# board1.net
KiCad netlist of a schematic drawn in EAGLE
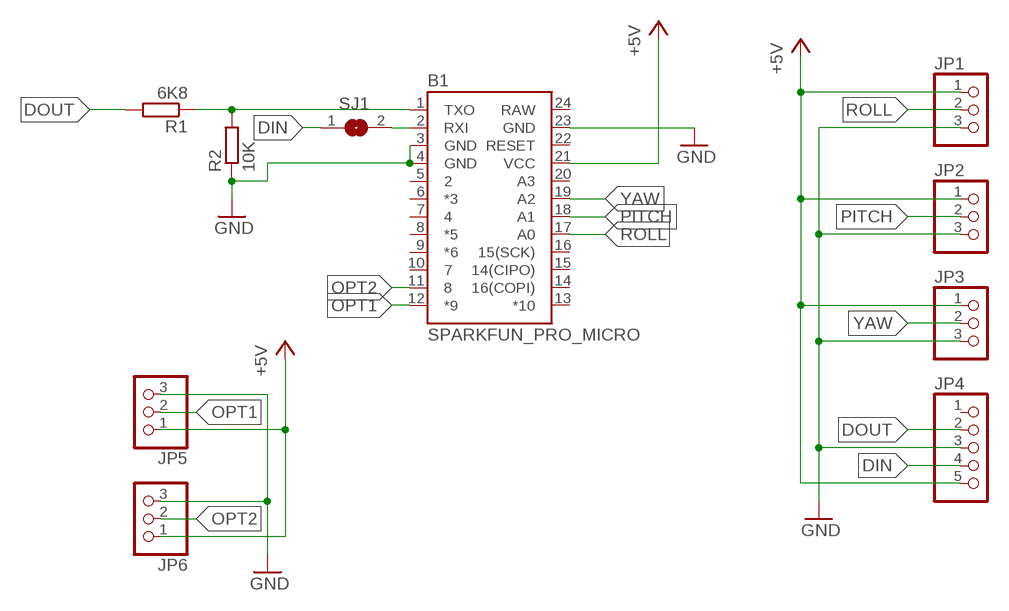
[diagram p0: schematic, sheet 1]

(export (version "E")
  (design (tool "Eeschema 10.0.6"))
  (components
    (comp (ref "B1")
      (value "SPARKFUN_PRO_MICRO")
      (footprint "eagle-import:SPARKFUN_PRO_MICRO")
      (libsource (lib "eagle-import") (part "SPARKFUN_PRO_MICRO"))
    )
    (comp (ref "JP1")
      (value "PINHD-1X3")
      (footprint "eagle-import:1X03")
      (libsource (lib "eagle-import") (part "PINHD-1X3"))
    )
    (comp (ref "JP2")
      (value "PINHD-1X3")
      (footprint "eagle-import:1X03")
      (libsource (lib "eagle-import") (part "PINHD-1X3"))
    )
    (comp (ref "JP3")
      (value "PINHD-1X3")
      (footprint "eagle-import:1X03")
      (libsource (lib "eagle-import") (part "PINHD-1X3"))
    )
    (comp (ref "JP4")
      (value "PINHD-1X5")
      (footprint "eagle-import:1X05")
      (libsource (lib "eagle-import") (part "PINHD-1X5"))
    )
    (comp (ref "JP5")
      (value "PINHD-1X3")
      (footprint "eagle-import:1X03")
      (libsource (lib "eagle-import") (part "PINHD-1X3"))
    )
    (comp (ref "JP6")
      (value "PINHD-1X3")
      (footprint "eagle-import:1X03")
      (libsource (lib "eagle-import") (part "PINHD-1X3"))
    )
    (comp (ref "R1")
      (value "6K8")
      (footprint "eagle-import:R0603")
      (libsource (lib "eagle-import") (part "R-EU_R0603"))
    )
    (comp (ref "R2")
      (value "10K")
      (footprint "eagle-import:R0603")
      (libsource (lib "eagle-import") (part "R-EU_R0603"))
    )
    (comp (ref "SJ1") (value "SJ") (footprint "eagle-import:SJ") (libsource (lib "eagle-import") (part "SJ")))
  )
  (nets
    (net (code "1") (name "+5V") (class "Default")
      (node (ref "B1") (pin "21") (pinfunction "VCC_21") (pintype "power_in"))
      (node (ref "JP1") (pin "1") (pinfunction "1_1") (pintype "passive"))
      (node (ref "JP2") (pin "1") (pinfunction "1_1") (pintype "passive"))
      (node (ref "JP3") (pin "1") (pinfunction "1_1") (pintype "passive"))
      (node (ref "JP4") (pin "5") (pinfunction "5_5") (pintype "passive"))
      (node (ref "JP5") (pin "1") (pinfunction "1_1") (pintype "passive"))
      (node (ref "JP6") (pin "1") (pinfunction "1_1") (pintype "passive"))
    )
    (net (code "2") (name "/RAW") (class "Default")
      (node (ref "B1") (pin "24") (pinfunction "RAW_24") (pintype "power_in"))
    )
    (net (code "3") (name "DIN") (class "Default")
      (node (ref "JP4") (pin "4") (pinfunction "4_4") (pintype "passive"))
      (node (ref "SJ1") (pin "1") (pinfunction "1_1") (pintype "passive"))
    )
    (net (code "4") (name "DOUT") (class "Default")
      (node (ref "JP4") (pin "2") (pinfunction "2_2") (pintype "passive"))
      (node (ref "R1") (pin "2") (pinfunction "2_2") (pintype "passive"))
    )
    (net (code "5") (name "GND") (class "Default")
      (node (ref "B1") (pin "23") (pinfunction "GND_23") (pintype "power_in"))
      (node (ref "B1") (pin "3") (pinfunction "GND_3") (pintype "power_in"))
      (node (ref "B1") (pin "4") (pinfunction "GND_4") (pintype "power_in"))
      (node (ref "JP1") (pin "3") (pinfunction "3_3") (pintype "passive"))
      (node (ref "JP2") (pin "3") (pinfunction "3_3") (pintype "passive"))
      (node (ref "JP3") (pin "3") (pinfunction "3_3") (pintype "passive"))
      (node (ref "JP4") (pin "3") (pinfunction "3_3") (pintype "passive"))
      (node (ref "JP5") (pin "3") (pinfunction "3_3") (pintype "passive"))
      (node (ref "JP6") (pin "3") (pinfunction "3_3") (pintype "passive"))
      (node (ref "R2") (pin "1") (pinfunction "1_1") (pintype "passive"))
    )
    (net (code "6") (name "Net-(B1-RXI)") (class "Default")
      (node (ref "B1") (pin "2") (pinfunction "RXI_2") (pintype "bidirectional"))
      (node (ref "SJ1") (pin "2") (pinfunction "2_2") (pintype "passive"))
    )
    (net (code "7") (name "Net-(B1-TXO)") (class "Default")
      (node (ref "B1") (pin "1") (pinfunction "TXO_1") (pintype "bidirectional"))
      (node (ref "R1") (pin "1") (pinfunction "1_1") (pintype "passive"))
      (node (ref "R2") (pin "2") (pinfunction "2_2") (pintype "passive"))
    )
    (net (code "8") (name "OPT1") (class "Default")
      (node (ref "B1") (pin "12") (pinfunction "*9_12") (pintype "bidirectional"))
      (node (ref "JP5") (pin "2") (pinfunction "2_2") (pintype "passive"))
    )
    (net (code "9") (name "OPT2") (class "Default")
      (node (ref "B1") (pin "11") (pinfunction "8_11") (pintype "bidirectional"))
      (node (ref "JP6") (pin "2") (pinfunction "2_2") (pintype "passive"))
    )
    (net (code "10") (name "PITCH") (class "Default")
      (node (ref "B1") (pin "18") (pinfunction "A1_18") (pintype "bidirectional"))
      (node (ref "JP2") (pin "2") (pinfunction "2_2") (pintype "passive"))
    )
    (net (code "11") (name "ROLL") (class "Default")
      (node (ref "B1") (pin "17") (pinfunction "A0_17") (pintype "bidirectional"))
      (node (ref "JP1") (pin "2") (pinfunction "2_2") (pintype "passive"))
    )
    (net (code "12") (name "YAW") (class "Default")
      (node (ref "B1") (pin "19") (pinfunction "A2_19") (pintype "bidirectional"))
      (node (ref "JP3") (pin "2") (pinfunction "2_2") (pintype "passive"))
    )
    (net (code "13") (name "unconnected-(B1-*3-Pad6)") (class "Default")
      (node (ref "B1") (pin "6") (pinfunction "*3_6") (pintype "bidirectional"))
    )
    (net (code "14") (name "unconnected-(B1-*5-Pad8)") (class "Default")
      (node (ref "B1") (pin "8") (pinfunction "*5_8") (pintype "bidirectional"))
    )
    (net (code "15") (name "unconnected-(B1-*6-Pad9)") (class "Default")
      (node (ref "B1") (pin "9") (pinfunction "*6_9") (pintype "bidirectional"))
    )
    (net (code "16") (name "unconnected-(B1-*10-Pad13)") (class "Default")
      (node (ref "B1") (pin "13") (pinfunction "*10_13") (pintype "bidirectional"))
    )
    (net (code "17") (name "unconnected-(B1-2-Pad5)") (class "Default")
      (node (ref "B1") (pin "5") (pinfunction "2_5") (pintype "bidirectional"))
    )
    (net (code "18") (name "unconnected-(B1-4-Pad7)") (class "Default")
      (node (ref "B1") (pin "7") (pinfunction "4_7") (pintype "bidirectional"))
    )
    (net (code "19") (name "unconnected-(B1-7-Pad10)") (class "Default")
      (node (ref "B1") (pin "10") (pinfunction "7_10") (pintype "bidirectional"))
    )
    (net (code "20") (name "unconnected-(B1-14(CIPO)-Pad15)") (class "Default")
      (node (ref "B1") (pin "15") (pinfunction "14(CIPO)_15") (pintype "bidirectional"))
    )
    (net (code "21") (name "unconnected-(B1-15(SCK)-Pad16)") (class "Default")
      (node (ref "B1") (pin "16") (pinfunction "15(SCK)_16") (pintype "bidirectional"))
    )
    (net (code "22") (name "unconnected-(B1-16(COPI)-Pad14)") (class "Default")
      (node (ref "B1") (pin "14") (pinfunction "16(COPI)_14") (pintype "bidirectional"))
    )
    (net (code "23") (name "unconnected-(B1-A3-Pad20)") (class "Default")
      (node (ref "B1") (pin "20") (pinfunction "A3_20") (pintype "bidirectional"))
    )
    (net (code "24") (name "unconnected-(B1-RESET-Pad22)") (class "Default")
      (node (ref "B1") (pin "22") (pinfunction "RESET_22") (pintype "bidirectional"))
    )
    (net (code "25") (name "unconnected-(JP4-Pad1)") (class "Default")
      (node (ref "JP4") (pin "1") (pinfunction "1_1") (pintype "passive"))
    )
  )
)
